# Sheet_2.net
KiCad netlist of a schematic drawn in EasyEDA
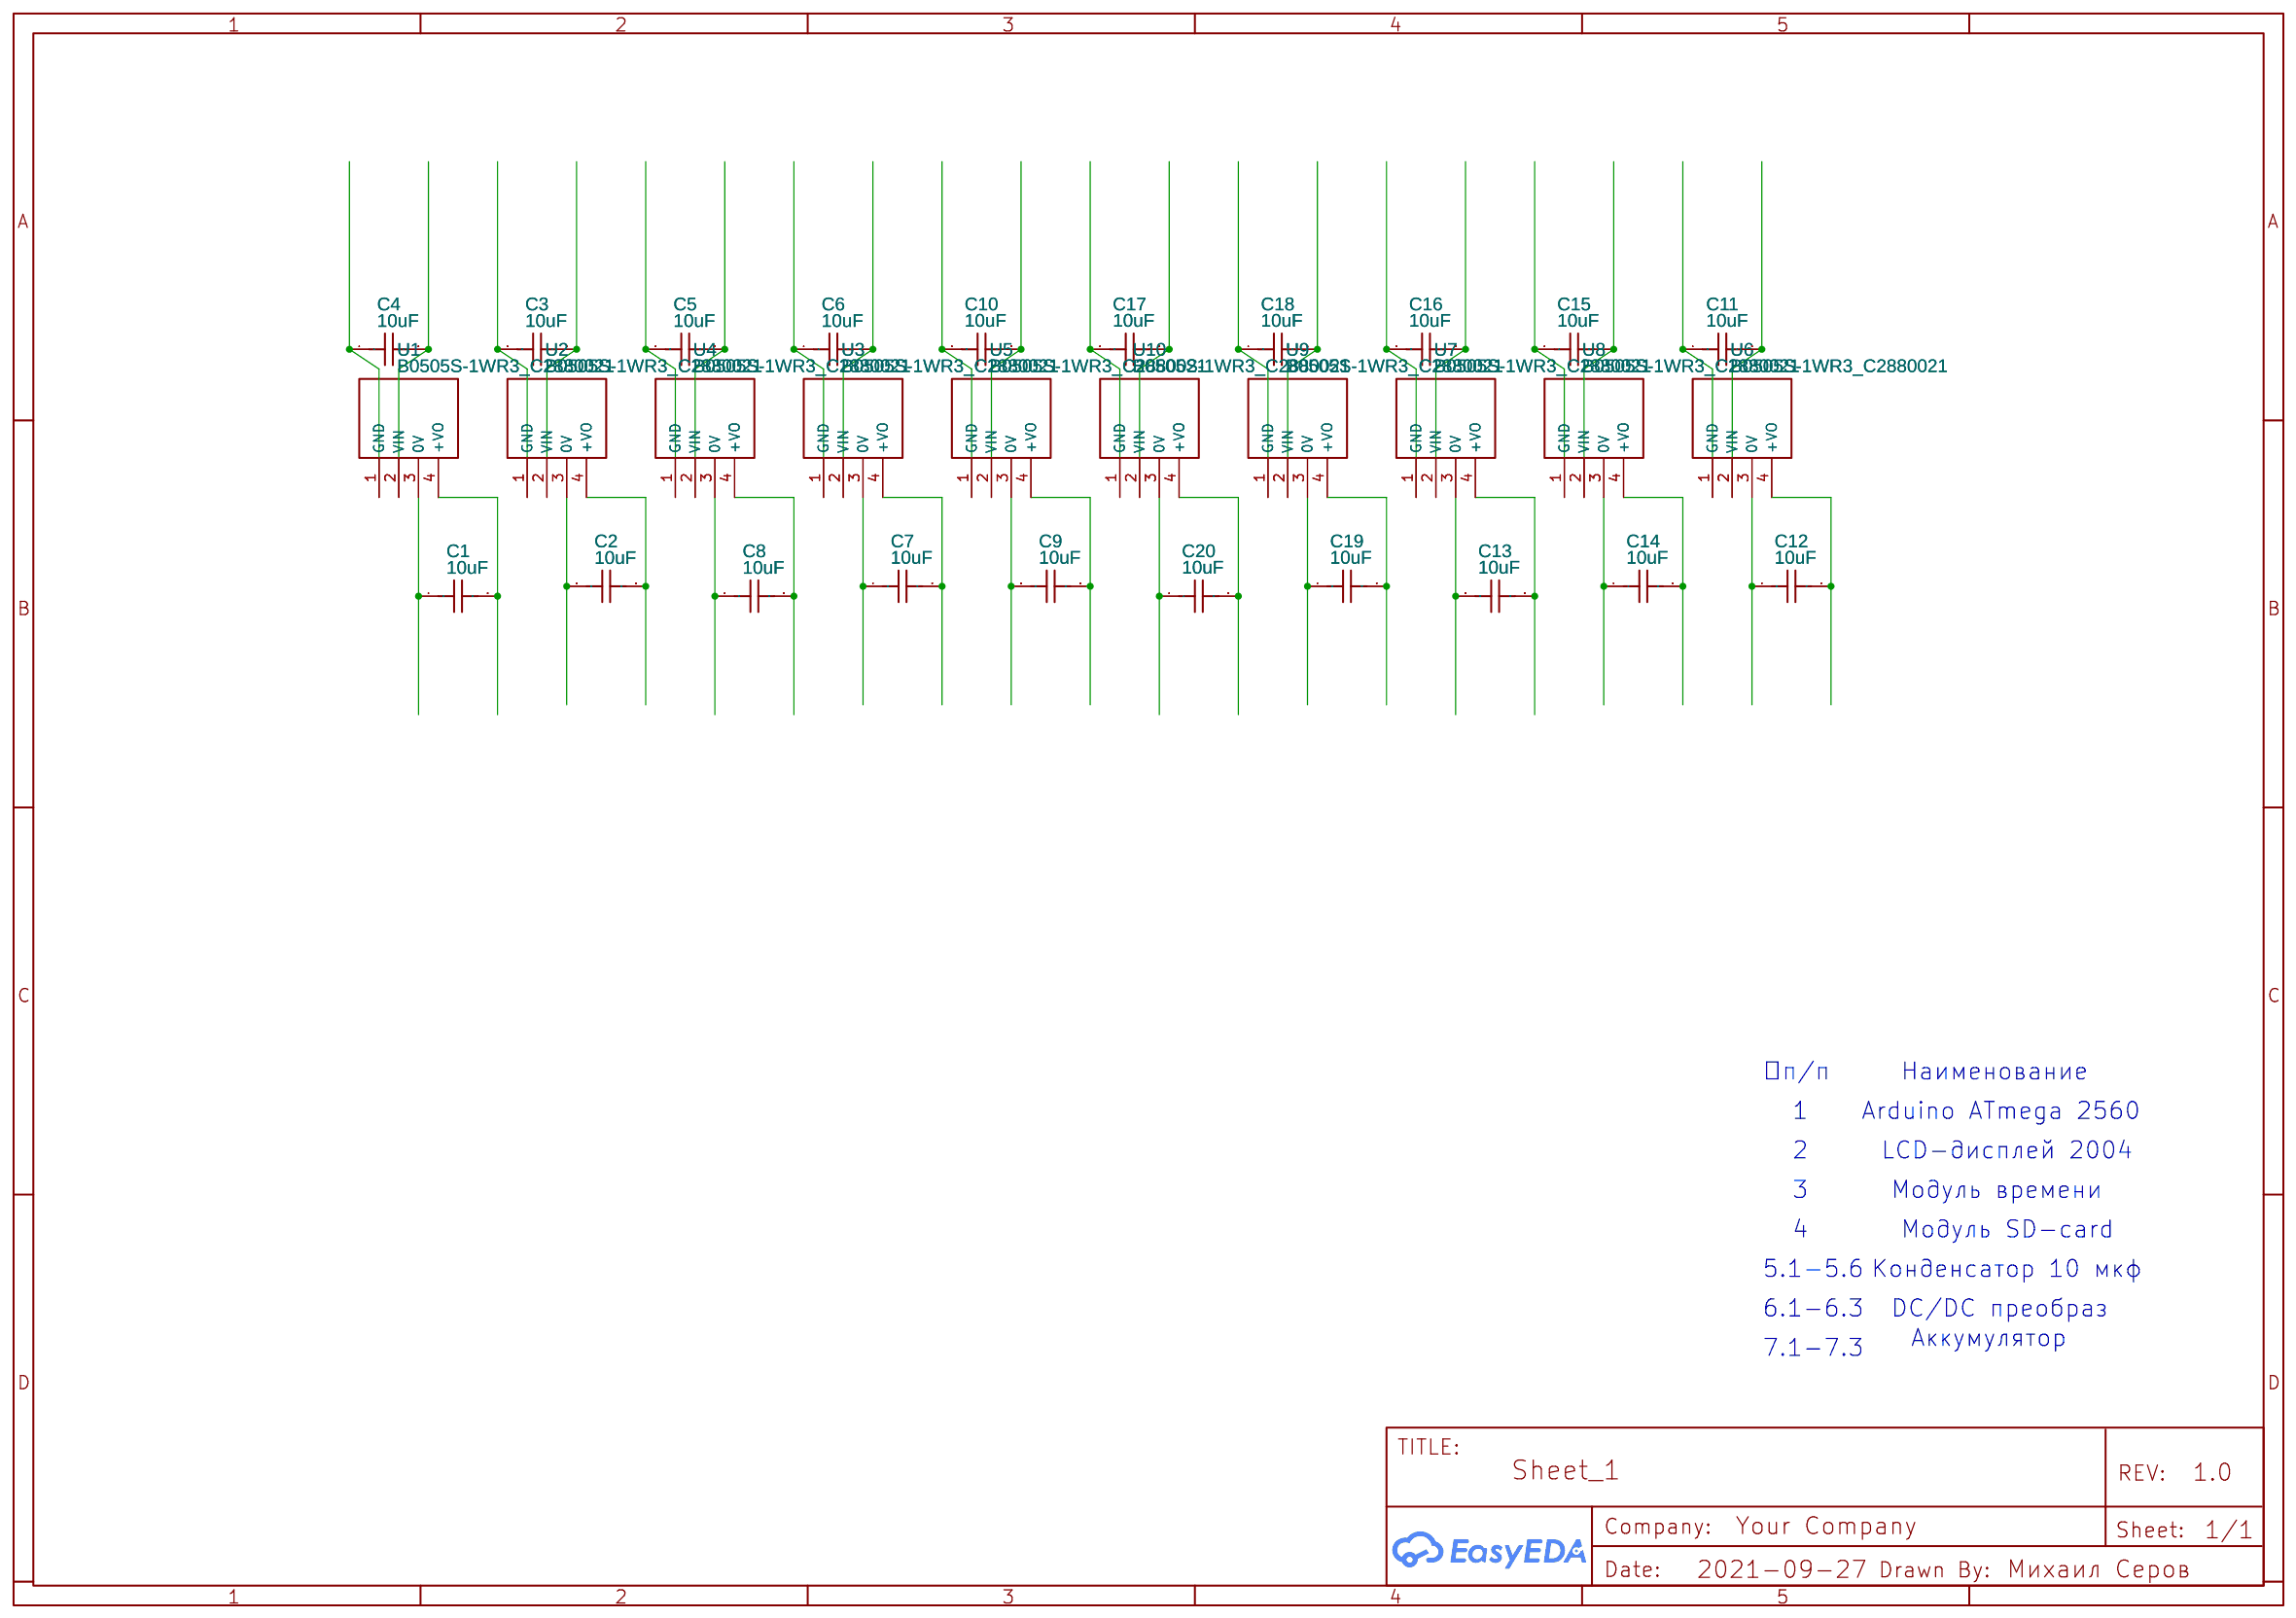
[diagram p0: schematic sheet]

(export (version "E")
  (design (tool "Eeschema 10.0.6"))
  (components
    (comp (ref "C1")
      (value "10uF")
      (fields
        (field (name "BOM_Manufacturer Part") "CS3216X7R106K250NRI")
        (field (name "BOM_Supplier Part") "C513767")
      )
      (libsource (lib "") (part "CS3216X7R106K250NRI"))
    )
    (comp (ref "C2")
      (value "10uF")
      (fields
        (field (name "BOM_Manufacturer Part") "CS3216X7R106K250NRI")
        (field (name "BOM_Supplier Part") "C513767")
      )
      (libsource (lib "") (part "CS3216X7R106K250NRI"))
    )
    (comp (ref "C3")
      (value "10uF")
      (fields
        (field (name "BOM_Manufacturer Part") "CS3216X7R106K250NRI")
        (field (name "BOM_Supplier Part") "C513767")
      )
      (libsource (lib "") (part "CS3216X7R106K250NRI"))
    )
    (comp (ref "C4")
      (value "10uF")
      (fields
        (field (name "BOM_Manufacturer Part") "CS3216X7R106K250NRI")
        (field (name "BOM_Supplier Part") "C513767")
      )
      (libsource (lib "") (part "CS3216X7R106K250NRI"))
    )
    (comp (ref "C5")
      (value "10uF")
      (fields
        (field (name "BOM_Manufacturer Part") "CS3216X7R106K250NRI")
        (field (name "BOM_Supplier Part") "C513767")
      )
      (libsource (lib "") (part "CS3216X7R106K250NRI"))
    )
    (comp (ref "C6")
      (value "10uF")
      (fields
        (field (name "BOM_Manufacturer Part") "CS3216X7R106K250NRI")
        (field (name "BOM_Supplier Part") "C513767")
      )
      (libsource (lib "") (part "CS3216X7R106K250NRI"))
    )
    (comp (ref "C7")
      (value "10uF")
      (fields
        (field (name "BOM_Manufacturer Part") "CS3216X7R106K250NRI")
        (field (name "BOM_Supplier Part") "C513767")
      )
      (libsource (lib "") (part "CS3216X7R106K250NRI"))
    )
    (comp (ref "C8")
      (value "10uF")
      (fields
        (field (name "BOM_Manufacturer Part") "CS3216X7R106K250NRI")
        (field (name "BOM_Supplier Part") "C513767")
      )
      (libsource (lib "") (part "CS3216X7R106K250NRI"))
    )
    (comp (ref "C9")
      (value "10uF")
      (fields
        (field (name "BOM_Manufacturer Part") "CS3216X7R106K250NRI")
        (field (name "BOM_Supplier Part") "C513767")
      )
      (libsource (lib "") (part "CS3216X7R106K250NRI"))
    )
    (comp (ref "C10")
      (value "10uF")
      (fields
        (field (name "BOM_Manufacturer Part") "CS3216X7R106K250NRI")
        (field (name "BOM_Supplier Part") "C513767")
      )
      (libsource (lib "") (part "CS3216X7R106K250NRI"))
    )
    (comp (ref "C11")
      (value "10uF")
      (fields
        (field (name "BOM_Manufacturer Part") "CS3216X7R106K250NRI")
        (field (name "BOM_Supplier Part") "C513767")
      )
      (libsource (lib "") (part "CS3216X7R106K250NRI"))
    )
    (comp (ref "C12")
      (value "10uF")
      (fields
        (field (name "BOM_Manufacturer Part") "CS3216X7R106K250NRI")
        (field (name "BOM_Supplier Part") "C513767")
      )
      (libsource (lib "") (part "CS3216X7R106K250NRI"))
    )
    (comp (ref "C13")
      (value "10uF")
      (fields
        (field (name "BOM_Manufacturer Part") "CS3216X7R106K250NRI")
        (field (name "BOM_Supplier Part") "C513767")
      )
      (libsource (lib "") (part "CS3216X7R106K250NRI"))
    )
    (comp (ref "C14")
      (value "10uF")
      (fields
        (field (name "BOM_Manufacturer Part") "CS3216X7R106K250NRI")
        (field (name "BOM_Supplier Part") "C513767")
      )
      (libsource (lib "") (part "CS3216X7R106K250NRI"))
    )
    (comp (ref "C15")
      (value "10uF")
      (fields
        (field (name "BOM_Manufacturer Part") "CS3216X7R106K250NRI")
        (field (name "BOM_Supplier Part") "C513767")
      )
      (libsource (lib "") (part "CS3216X7R106K250NRI"))
    )
    (comp (ref "C16")
      (value "10uF")
      (fields
        (field (name "BOM_Manufacturer Part") "CS3216X7R106K250NRI")
        (field (name "BOM_Supplier Part") "C513767")
      )
      (libsource (lib "") (part "CS3216X7R106K250NRI"))
    )
    (comp (ref "C17")
      (value "10uF")
      (fields
        (field (name "BOM_Manufacturer Part") "CS3216X7R106K250NRI")
        (field (name "BOM_Supplier Part") "C513767")
      )
      (libsource (lib "") (part "CS3216X7R106K250NRI"))
    )
    (comp (ref "C18")
      (value "10uF")
      (fields
        (field (name "BOM_Manufacturer Part") "CS3216X7R106K250NRI")
        (field (name "BOM_Supplier Part") "C513767")
      )
      (libsource (lib "") (part "CS3216X7R106K250NRI"))
    )
    (comp (ref "C19")
      (value "10uF")
      (fields
        (field (name "BOM_Manufacturer Part") "CS3216X7R106K250NRI")
        (field (name "BOM_Supplier Part") "C513767")
      )
      (libsource (lib "") (part "CS3216X7R106K250NRI"))
    )
    (comp (ref "C20")
      (value "10uF")
      (fields
        (field (name "BOM_Manufacturer Part") "CS3216X7R106K250NRI")
        (field (name "BOM_Supplier Part") "C513767")
      )
      (libsource (lib "") (part "CS3216X7R106K250NRI"))
    )
    (comp (ref "U1")
      (value "B0505S-1WR3_C2880021")
      (fields
        (field (name "BOM_Manufacturer Part") "B0505S-1WR3")
        (field (name "BOM_Supplier Part") "C2880021")
      )
      (libsource (lib "") (part "B0505S-1WR3_C2880021"))
    )
    (comp (ref "U2")
      (value "B0505S-1WR3_C2880021")
      (fields
        (field (name "BOM_Manufacturer Part") "B0505S-1WR3")
        (field (name "BOM_Supplier Part") "C2880021")
      )
      (libsource (lib "") (part "B0505S-1WR3_C2880021"))
    )
    (comp (ref "U3")
      (value "B0505S-1WR3_C2880021")
      (fields
        (field (name "BOM_Manufacturer Part") "B0505S-1WR3")
        (field (name "BOM_Supplier Part") "C2880021")
      )
      (libsource (lib "") (part "B0505S-1WR3_C2880021"))
    )
    (comp (ref "U4")
      (value "B0505S-1WR3_C2880021")
      (fields
        (field (name "BOM_Manufacturer Part") "B0505S-1WR3")
        (field (name "BOM_Supplier Part") "C2880021")
      )
      (libsource (lib "") (part "B0505S-1WR3_C2880021"))
    )
    (comp (ref "U5")
      (value "B0505S-1WR3_C2880021")
      (fields
        (field (name "BOM_Manufacturer Part") "B0505S-1WR3")
        (field (name "BOM_Supplier Part") "C2880021")
      )
      (libsource (lib "") (part "B0505S-1WR3_C2880021"))
    )
    (comp (ref "U6")
      (value "B0505S-1WR3_C2880021")
      (fields
        (field (name "BOM_Manufacturer Part") "B0505S-1WR3")
        (field (name "BOM_Supplier Part") "C2880021")
      )
      (libsource (lib "") (part "B0505S-1WR3_C2880021"))
    )
    (comp (ref "U7")
      (value "B0505S-1WR3_C2880021")
      (fields
        (field (name "BOM_Manufacturer Part") "B0505S-1WR3")
        (field (name "BOM_Supplier Part") "C2880021")
      )
      (libsource (lib "") (part "B0505S-1WR3_C2880021"))
    )
    (comp (ref "U8")
      (value "B0505S-1WR3_C2880021")
      (fields
        (field (name "BOM_Manufacturer Part") "B0505S-1WR3")
        (field (name "BOM_Supplier Part") "C2880021")
      )
      (libsource (lib "") (part "B0505S-1WR3_C2880021"))
    )
    (comp (ref "U9")
      (value "B0505S-1WR3_C2880021")
      (fields
        (field (name "BOM_Manufacturer Part") "B0505S-1WR3")
        (field (name "BOM_Supplier Part") "C2880021")
      )
      (libsource (lib "") (part "B0505S-1WR3_C2880021"))
    )
    (comp (ref "U10")
      (value "B0505S-1WR3_C2880021")
      (fields
        (field (name "BOM_Manufacturer Part") "B0505S-1WR3")
        (field (name "BOM_Supplier Part") "C2880021")
      )
      (libsource (lib "") (part "B0505S-1WR3_C2880021"))
    )
  )
  (nets
    (net (code "1") (name "Net-(U1-+VO)") (class "Default")
      (node (ref "C1") (pin "2") (pinfunction "2_2") (pintype "unspecified"))
      (node (ref "U1") (pin "4") (pinfunction "+VO_4") (pintype "unspecified"))
    )
    (net (code "2") (name "Net-(U1-0V)") (class "Default")
      (node (ref "C1") (pin "1") (pinfunction "1_1") (pintype "unspecified"))
      (node (ref "U1") (pin "3") (pinfunction "0V_3") (pintype "unspecified"))
    )
    (net (code "3") (name "Net-(U1-GND)") (class "Default")
      (node (ref "C4") (pin "1") (pinfunction "1_1") (pintype "unspecified"))
      (node (ref "U1") (pin "1") (pinfunction "GND_1") (pintype "unspecified"))
    )
    (net (code "4") (name "Net-(U1-VIN)") (class "Default")
      (node (ref "C4") (pin "2") (pinfunction "2_2") (pintype "unspecified"))
      (node (ref "U1") (pin "2") (pinfunction "VIN_2") (pintype "unspecified"))
    )
    (net (code "5") (name "Net-(U2-+VO)") (class "Default")
      (node (ref "C2") (pin "2") (pinfunction "2_2") (pintype "unspecified"))
      (node (ref "U2") (pin "4") (pinfunction "+VO_4") (pintype "unspecified"))
    )
    (net (code "6") (name "Net-(U2-0V)") (class "Default")
      (node (ref "C2") (pin "1") (pinfunction "1_1") (pintype "unspecified"))
      (node (ref "U2") (pin "3") (pinfunction "0V_3") (pintype "unspecified"))
    )
    (net (code "7") (name "Net-(U2-GND)") (class "Default")
      (node (ref "C3") (pin "1") (pinfunction "1_1") (pintype "unspecified"))
      (node (ref "U2") (pin "1") (pinfunction "GND_1") (pintype "unspecified"))
    )
    (net (code "8") (name "Net-(U2-VIN)") (class "Default")
      (node (ref "C3") (pin "2") (pinfunction "2_2") (pintype "unspecified"))
      (node (ref "U2") (pin "2") (pinfunction "VIN_2") (pintype "unspecified"))
    )
    (net (code "9") (name "Net-(U3-+VO)") (class "Default")
      (node (ref "C7") (pin "2") (pinfunction "2_2") (pintype "unspecified"))
      (node (ref "U3") (pin "4") (pinfunction "+VO_4") (pintype "unspecified"))
    )
    (net (code "10") (name "Net-(U3-0V)") (class "Default")
      (node (ref "C7") (pin "1") (pinfunction "1_1") (pintype "unspecified"))
      (node (ref "U3") (pin "3") (pinfunction "0V_3") (pintype "unspecified"))
    )
    (net (code "11") (name "Net-(U3-GND)") (class "Default")
      (node (ref "C6") (pin "1") (pinfunction "1_1") (pintype "unspecified"))
      (node (ref "U3") (pin "1") (pinfunction "GND_1") (pintype "unspecified"))
    )
    (net (code "12") (name "Net-(U3-VIN)") (class "Default")
      (node (ref "C6") (pin "2") (pinfunction "2_2") (pintype "unspecified"))
      (node (ref "U3") (pin "2") (pinfunction "VIN_2") (pintype "unspecified"))
    )
    (net (code "13") (name "Net-(U4-+VO)") (class "Default")
      (node (ref "C8") (pin "2") (pinfunction "2_2") (pintype "unspecified"))
      (node (ref "U4") (pin "4") (pinfunction "+VO_4") (pintype "unspecified"))
    )
    (net (code "14") (name "Net-(U4-0V)") (class "Default")
      (node (ref "C8") (pin "1") (pinfunction "1_1") (pintype "unspecified"))
      (node (ref "U4") (pin "3") (pinfunction "0V_3") (pintype "unspecified"))
    )
    (net (code "15") (name "Net-(U4-GND)") (class "Default")
      (node (ref "C5") (pin "1") (pinfunction "1_1") (pintype "unspecified"))
      (node (ref "U4") (pin "1") (pinfunction "GND_1") (pintype "unspecified"))
    )
    (net (code "16") (name "Net-(U4-VIN)") (class "Default")
      (node (ref "C5") (pin "2") (pinfunction "2_2") (pintype "unspecified"))
      (node (ref "U4") (pin "2") (pinfunction "VIN_2") (pintype "unspecified"))
    )
    (net (code "17") (name "Net-(U5-+VO)") (class "Default")
      (node (ref "C9") (pin "2") (pinfunction "2_2") (pintype "unspecified"))
      (node (ref "U5") (pin "4") (pinfunction "+VO_4") (pintype "unspecified"))
    )
    (net (code "18") (name "Net-(U5-0V)") (class "Default")
      (node (ref "C9") (pin "1") (pinfunction "1_1") (pintype "unspecified"))
      (node (ref "U5") (pin "3") (pinfunction "0V_3") (pintype "unspecified"))
    )
    (net (code "19") (name "Net-(U5-GND)") (class "Default")
      (node (ref "C10") (pin "1") (pinfunction "1_1") (pintype "unspecified"))
      (node (ref "U5") (pin "1") (pinfunction "GND_1") (pintype "unspecified"))
    )
    (net (code "20") (name "Net-(U5-VIN)") (class "Default")
      (node (ref "C10") (pin "2") (pinfunction "2_2") (pintype "unspecified"))
      (node (ref "U5") (pin "2") (pinfunction "VIN_2") (pintype "unspecified"))
    )
    (net (code "21") (name "Net-(U6-+VO)") (class "Default")
      (node (ref "C12") (pin "2") (pinfunction "2_2") (pintype "unspecified"))
      (node (ref "U6") (pin "4") (pinfunction "+VO_4") (pintype "unspecified"))
    )
    (net (code "22") (name "Net-(U6-0V)") (class "Default")
      (node (ref "C12") (pin "1") (pinfunction "1_1") (pintype "unspecified"))
      (node (ref "U6") (pin "3") (pinfunction "0V_3") (pintype "unspecified"))
    )
    (net (code "23") (name "Net-(U6-GND)") (class "Default")
      (node (ref "C11") (pin "1") (pinfunction "1_1") (pintype "unspecified"))
      (node (ref "U6") (pin "1") (pinfunction "GND_1") (pintype "unspecified"))
    )
    (net (code "24") (name "Net-(U6-VIN)") (class "Default")
      (node (ref "C11") (pin "2") (pinfunction "2_2") (pintype "unspecified"))
      (node (ref "U6") (pin "2") (pinfunction "VIN_2") (pintype "unspecified"))
    )
    (net (code "25") (name "Net-(U7-+VO)") (class "Default")
      (node (ref "C13") (pin "2") (pinfunction "2_2") (pintype "unspecified"))
      (node (ref "U7") (pin "4") (pinfunction "+VO_4") (pintype "unspecified"))
    )
    (net (code "26") (name "Net-(U7-0V)") (class "Default")
      (node (ref "C13") (pin "1") (pinfunction "1_1") (pintype "unspecified"))
      (node (ref "U7") (pin "3") (pinfunction "0V_3") (pintype "unspecified"))
    )
    (net (code "27") (name "Net-(U7-GND)") (class "Default")
      (node (ref "C16") (pin "1") (pinfunction "1_1") (pintype "unspecified"))
      (node (ref "U7") (pin "1") (pinfunction "GND_1") (pintype "unspecified"))
    )
    (net (code "28") (name "Net-(U7-VIN)") (class "Default")
      (node (ref "C16") (pin "2") (pinfunction "2_2") (pintype "unspecified"))
      (node (ref "U7") (pin "2") (pinfunction "VIN_2") (pintype "unspecified"))
    )
    (net (code "29") (name "Net-(U8-+VO)") (class "Default")
      (node (ref "C14") (pin "2") (pinfunction "2_2") (pintype "unspecified"))
      (node (ref "U8") (pin "4") (pinfunction "+VO_4") (pintype "unspecified"))
    )
    (net (code "30") (name "Net-(U8-0V)") (class "Default")
      (node (ref "C14") (pin "1") (pinfunction "1_1") (pintype "unspecified"))
      (node (ref "U8") (pin "3") (pinfunction "0V_3") (pintype "unspecified"))
    )
    (net (code "31") (name "Net-(U8-GND)") (class "Default")
      (node (ref "C15") (pin "1") (pinfunction "1_1") (pintype "unspecified"))
      (node (ref "U8") (pin "1") (pinfunction "GND_1") (pintype "unspecified"))
    )
    (net (code "32") (name "Net-(U8-VIN)") (class "Default")
      (node (ref "C15") (pin "2") (pinfunction "2_2") (pintype "unspecified"))
      (node (ref "U8") (pin "2") (pinfunction "VIN_2") (pintype "unspecified"))
    )
    (net (code "33") (name "Net-(U9-+VO)") (class "Default")
      (node (ref "C19") (pin "2") (pinfunction "2_2") (pintype "unspecified"))
      (node (ref "U9") (pin "4") (pinfunction "+VO_4") (pintype "unspecified"))
    )
    (net (code "34") (name "Net-(U9-0V)") (class "Default")
      (node (ref "C19") (pin "1") (pinfunction "1_1") (pintype "unspecified"))
      (node (ref "U9") (pin "3") (pinfunction "0V_3") (pintype "unspecified"))
    )
    (net (code "35") (name "Net-(U9-GND)") (class "Default")
      (node (ref "C18") (pin "1") (pinfunction "1_1") (pintype "unspecified"))
      (node (ref "U9") (pin "1") (pinfunction "GND_1") (pintype "unspecified"))
    )
    (net (code "36") (name "Net-(U9-VIN)") (class "Default")
      (node (ref "C18") (pin "2") (pinfunction "2_2") (pintype "unspecified"))
      (node (ref "U9") (pin "2") (pinfunction "VIN_2") (pintype "unspecified"))
    )
    (net (code "37") (name "Net-(U10-+VO)") (class "Default")
      (node (ref "C20") (pin "2") (pinfunction "2_2") (pintype "unspecified"))
      (node (ref "U10") (pin "4") (pinfunction "+VO_4") (pintype "unspecified"))
    )
    (net (code "38") (name "Net-(U10-0V)") (class "Default")
      (node (ref "C20") (pin "1") (pinfunction "1_1") (pintype "unspecified"))
      (node (ref "U10") (pin "3") (pinfunction "0V_3") (pintype "unspecified"))
    )
    (net (code "39") (name "Net-(U10-GND)") (class "Default")
      (node (ref "C17") (pin "1") (pinfunction "1_1") (pintype "unspecified"))
      (node (ref "U10") (pin "1") (pinfunction "GND_1") (pintype "unspecified"))
    )
    (net (code "40") (name "Net-(U10-VIN)") (class "Default")
      (node (ref "C17") (pin "2") (pinfunction "2_2") (pintype "unspecified"))
      (node (ref "U10") (pin "2") (pinfunction "VIN_2") (pintype "unspecified"))
    )
  )
)
